# signalgen.net
KiCad netlist of a schematic drawn in EAGLE
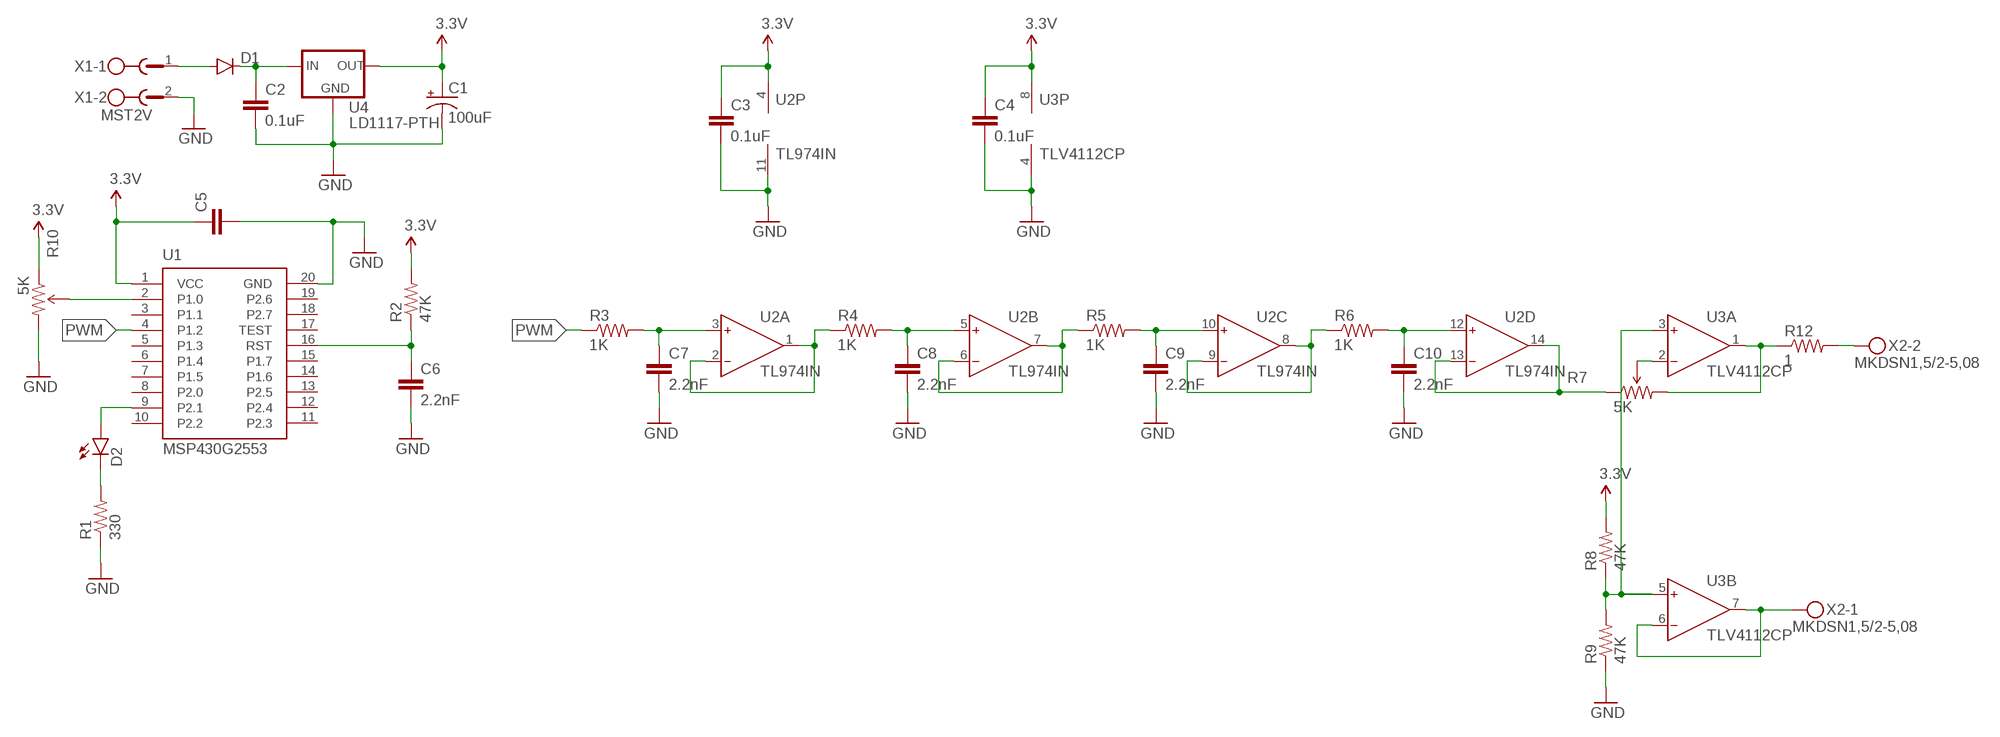
[diagram p0: schematic, sheet 1]

(export (version "E")
  (design (tool "Eeschema 10.0.6"))
  (components
    (comp (ref "C1")
      (value "100uF")
      (footprint "eagle-import:CPOL-RADIAL-100UF-25V")
      (libsource (lib "eagle-import") (part "CAP_POLPTH1"))
    )
    (comp (ref "C2")
      (value "0.1uF")
      (footprint "eagle-import:CAP-PTH-SMALL")
      (libsource (lib "eagle-import") (part "CAPPTH"))
    )
    (comp (ref "C3")
      (value "0.1uF")
      (footprint "eagle-import:CAP-PTH-SMALL")
      (libsource (lib "eagle-import") (part "CAPPTH"))
    )
    (comp (ref "C4")
      (value "0.1uF")
      (footprint "eagle-import:CAP-PTH-SMALL")
      (libsource (lib "eagle-import") (part "CAPPTH"))
    )
    (comp (ref "C5")
      (value "CAPPTH")
      (footprint "eagle-import:CAP-PTH-SMALL")
      (libsource (lib "eagle-import") (part "CAPPTH"))
    )
    (comp (ref "C6")
      (value "2.2nF")
      (footprint "eagle-import:CAP-PTH-SMALL")
      (libsource (lib "eagle-import") (part "CAPPTH"))
    )
    (comp (ref "C7")
      (value "2.2nF")
      (footprint "eagle-import:CAP-PTH-SMALL")
      (libsource (lib "eagle-import") (part "CAPPTH"))
    )
    (comp (ref "C8")
      (value "2.2nF")
      (footprint "eagle-import:CAP-PTH-SMALL")
      (libsource (lib "eagle-import") (part "CAPPTH"))
    )
    (comp (ref "C9")
      (value "2.2nF")
      (footprint "eagle-import:CAP-PTH-SMALL")
      (libsource (lib "eagle-import") (part "CAPPTH"))
    )
    (comp (ref "C10")
      (value "2.2nF")
      (footprint "eagle-import:CAP-PTH-SMALL")
      (libsource (lib "eagle-import") (part "CAPPTH"))
    )
    (comp (ref "D1")
      (value "DIODEPTH")
      (footprint "eagle-import:DIODE-1N4001")
      (libsource (lib "eagle-import") (part "DIODEPTH"))
    )
    (comp (ref "D2")
      (value "LED-3MM-NO_SILK")
      (footprint "eagle-import:LED3MM-NS")
      (libsource (lib "eagle-import") (part "LED-3MM-NO_SILK"))
    )
    (comp (ref "R1")
      (value "330")
      (footprint "eagle-import:AXIAL-0.1")
      (libsource (lib "eagle-import") (part "1KOHM-1/4W-1%(PTH)VERT"))
    )
    (comp (ref "R2")
      (value "47K")
      (footprint "eagle-import:AXIAL-0.3")
      (libsource (lib "eagle-import") (part "1KOHM-1/4W-1%(PTH)"))
    )
    (comp (ref "R3")
      (value "1K")
      (footprint "eagle-import:AXIAL-0.1")
      (libsource (lib "eagle-import") (part "1KOHM-1/4W-1%(PTH)VERT"))
    )
    (comp (ref "R4")
      (value "1K")
      (footprint "eagle-import:AXIAL-0.3")
      (libsource (lib "eagle-import") (part "1KOHM-1/4W-1%(PTH)"))
    )
    (comp (ref "R5")
      (value "1K")
      (footprint "eagle-import:AXIAL-0.1")
      (libsource (lib "eagle-import") (part "1KOHM-1/4W-1%(PTH)VERT"))
    )
    (comp (ref "R6")
      (value "1K")
      (footprint "eagle-import:AXIAL-0.3")
      (libsource (lib "eagle-import") (part "1KOHM-1/4W-1%(PTH)"))
    )
    (comp (ref "R7")
      (value "5K")
      (footprint "eagle-import:TRIM_POT_PTH")
      (libsource (lib "eagle-import") (part "TRIMPOTPTH"))
    )
    (comp (ref "R8")
      (value "47K")
      (footprint "eagle-import:AXIAL-0.3")
      (libsource (lib "eagle-import") (part "1KOHM-1/4W-1%(PTH)"))
    )
    (comp (ref "R9")
      (value "47K")
      (footprint "eagle-import:AXIAL-0.3")
      (libsource (lib "eagle-import") (part "1KOHM-1/4W-1%(PTH)"))
    )
    (comp (ref "R10")
      (value "5K")
      (footprint "eagle-import:TRIM_POT_PTH")
      (libsource (lib "eagle-import") (part "TRIMPOTPTH"))
    )
    (comp (ref "R12")
      (value "1")
      (footprint "eagle-import:AXIAL-0.6")
      (libsource (lib "eagle-import") (part "RESISTORPTH-1W"))
    )
    (comp (ref "U1")
      (value "MSP430G2553")
      (footprint "eagle-import:DIP-20")
      (libsource (lib "eagle-import") (part "MSP430G2553"))
    )
    (comp (ref "U2")
      (value "TL974IN")
      (footprint "eagle-import:DIP-14")
      (libsource (lib "eagle-import") (part "TL974IN"))
    )
    (comp (ref "U3")
      (value "TLV4112CP")
      (footprint "eagle-import:DIP-8")
      (libsource (lib "eagle-import") (part "TLV4112CP"))
    )
    (comp (ref "U4")
      (value "LD1117-PTH")
      (footprint "eagle-import:TO-220ABS")
      (libsource (lib "eagle-import") (part "LD1117-PTH"))
    )
    (comp (ref "X1")
      (value "MST2V")
      (footprint "eagle-import:MSTBV2")
      (libsource (lib "eagle-import") (part "MST2V"))
    )
    (comp (ref "X2")
      (value "MKDSN1,5/2-5,08")
      (footprint "eagle-import:MKDSN1,5_2-5,08")
      (libsource (lib "eagle-import") (part "MKDSN1,5/2-5,08"))
    )
  )
  (nets
    (net (code "1") (name "3.3V") (class "Default")
      (node (ref "C1") (pin "1") (pinfunction "+_1") (pintype "passive"))
      (node (ref "C3") (pin "1") (pinfunction "1_1") (pintype "passive"))
      (node (ref "C4") (pin "1") (pinfunction "1_1") (pintype "passive"))
      (node (ref "C5") (pin "1") (pinfunction "1_1") (pintype "passive"))
      (node (ref "R10") (pin "1") (pinfunction "CCW_1") (pintype "passive"))
      (node (ref "R2") (pin "P$2") (pinfunction "2_P$2") (pintype "passive"))
      (node (ref "R8") (pin "P$2") (pinfunction "2_P$2") (pintype "passive"))
      (node (ref "U1") (pin "1") (pinfunction "VCC_1") (pintype "bidirectional"))
      (node (ref "U2") (pin "4") (pinfunction "V+_4") (pintype "power_in"))
      (node (ref "U3") (pin "8") (pinfunction "V+_8") (pintype "power_in"))
      (node (ref "U4") (pin "2") (pinfunction "OUT_2") (pintype "passive"))
    )
    (net (code "2") (name "GND") (class "Default")
      (node (ref "C1") (pin "2") (pinfunction "-_2") (pintype "passive"))
      (node (ref "C10") (pin "2") (pinfunction "2_2") (pintype "passive"))
      (node (ref "C2") (pin "2") (pinfunction "2_2") (pintype "passive"))
      (node (ref "C3") (pin "2") (pinfunction "2_2") (pintype "passive"))
      (node (ref "C4") (pin "2") (pinfunction "2_2") (pintype "passive"))
      (node (ref "C5") (pin "2") (pinfunction "2_2") (pintype "passive"))
      (node (ref "C6") (pin "2") (pinfunction "2_2") (pintype "passive"))
      (node (ref "C7") (pin "2") (pinfunction "2_2") (pintype "passive"))
      (node (ref "C8") (pin "2") (pinfunction "2_2") (pintype "passive"))
      (node (ref "C9") (pin "2") (pinfunction "2_2") (pintype "passive"))
      (node (ref "R1") (pin "P$1") (pinfunction "1_P$1") (pintype "passive"))
      (node (ref "R10") (pin "3") (pinfunction "CW_3") (pintype "passive"))
      (node (ref "R9") (pin "P$1") (pinfunction "1_P$1") (pintype "passive"))
      (node (ref "U1") (pin "20") (pinfunction "GND_20") (pintype "bidirectional"))
      (node (ref "U2") (pin "11") (pinfunction "V-_11") (pintype "power_in"))
      (node (ref "U3") (pin "4") (pinfunction "V-_4") (pintype "power_in"))
      (node (ref "U4") (pin "1") (pinfunction "GND_1") (pintype "input"))
      (node (ref "X1") (pin "2") (pinfunction "1_2") (pintype "passive"))
    )
    (net (code "3") (name "Net-(D1-PadA)") (class "Default")
      (node (ref "D1") (pin "A") (pinfunction "A_A") (pintype "passive"))
      (node (ref "X1") (pin "1") (pinfunction "1_1") (pintype "passive"))
    )
    (net (code "4") (name "Net-(D2-C)") (class "Default")
      (node (ref "D2") (pin "K") (pinfunction "C_K") (pintype "passive"))
      (node (ref "R1") (pin "P$2") (pinfunction "2_P$2") (pintype "passive"))
    )
    (net (code "5") (name "Net-(R2-1)") (class "Default")
      (node (ref "C6") (pin "1") (pinfunction "1_1") (pintype "passive"))
      (node (ref "R2") (pin "P$1") (pinfunction "1_P$1") (pintype "passive"))
      (node (ref "U1") (pin "16") (pinfunction "RST_16") (pintype "bidirectional"))
    )
    (net (code "6") (name "Net-(R3-2)") (class "Default")
      (node (ref "C7") (pin "1") (pinfunction "1_1") (pintype "passive"))
      (node (ref "R3") (pin "P$2") (pinfunction "2_P$2") (pintype "passive"))
      (node (ref "U2") (pin "3") (pinfunction "IN+_3") (pintype "input"))
    )
    (net (code "7") (name "Net-(R4-1)") (class "Default")
      (node (ref "R4") (pin "P$1") (pinfunction "1_P$1") (pintype "passive"))
      (node (ref "U2") (pin "1") (pinfunction "OUT_1") (pintype "output"))
      (node (ref "U2") (pin "2") (pinfunction "IN-_2") (pintype "input"))
    )
    (net (code "8") (name "Net-(R4-2)") (class "Default")
      (node (ref "C8") (pin "1") (pinfunction "1_1") (pintype "passive"))
      (node (ref "R4") (pin "P$2") (pinfunction "2_P$2") (pintype "passive"))
      (node (ref "U2") (pin "5") (pinfunction "IN+_5") (pintype "input"))
    )
    (net (code "9") (name "Net-(R5-1)") (class "Default")
      (node (ref "R5") (pin "P$1") (pinfunction "1_P$1") (pintype "passive"))
      (node (ref "U2") (pin "6") (pinfunction "IN-_6") (pintype "input"))
      (node (ref "U2") (pin "7") (pinfunction "OUT_7") (pintype "output"))
    )
    (net (code "10") (name "Net-(R5-2)") (class "Default")
      (node (ref "C9") (pin "1") (pinfunction "1_1") (pintype "passive"))
      (node (ref "R5") (pin "P$2") (pinfunction "2_P$2") (pintype "passive"))
      (node (ref "U2") (pin "10") (pinfunction "IN+_10") (pintype "input"))
    )
    (net (code "11") (name "Net-(R6-1)") (class "Default")
      (node (ref "R6") (pin "P$1") (pinfunction "1_P$1") (pintype "passive"))
      (node (ref "U2") (pin "8") (pinfunction "OUT_8") (pintype "output"))
      (node (ref "U2") (pin "9") (pinfunction "IN-_9") (pintype "input"))
    )
    (net (code "12") (name "Net-(R6-2)") (class "Default")
      (node (ref "C10") (pin "1") (pinfunction "1_1") (pintype "passive"))
      (node (ref "R6") (pin "P$2") (pinfunction "2_P$2") (pintype "passive"))
      (node (ref "U2") (pin "12") (pinfunction "IN+_12") (pintype "input"))
    )
    (net (code "13") (name "Net-(R7-CCW)") (class "Default")
      (node (ref "R7") (pin "1") (pinfunction "CCW_1") (pintype "passive"))
      (node (ref "U2") (pin "13") (pinfunction "IN-_13") (pintype "input"))
      (node (ref "U2") (pin "14") (pinfunction "OUT_14") (pintype "output"))
    )
    (net (code "14") (name "Net-(R7-WIPER)") (class "Default")
      (node (ref "R7") (pin "2") (pinfunction "WIPER_2") (pintype "passive"))
      (node (ref "U3") (pin "2") (pinfunction "IN-_2") (pintype "input"))
    )
    (net (code "15") (name "Net-(R8-1)") (class "Default")
      (node (ref "R8") (pin "P$1") (pinfunction "1_P$1") (pintype "passive"))
      (node (ref "R9") (pin "P$2") (pinfunction "2_P$2") (pintype "passive"))
      (node (ref "U3") (pin "3") (pinfunction "IN+_3") (pintype "input"))
      (node (ref "U3") (pin "5") (pinfunction "IN+_5") (pintype "input"))
    )
    (net (code "16") (name "Net-(R10-WIPER)") (class "Default")
      (node (ref "R10") (pin "2") (pinfunction "WIPER_2") (pintype "passive"))
      (node (ref "U1") (pin "2") (pinfunction "P1.0_2") (pintype "bidirectional"))
    )
    (net (code "17") (name "Net-(R12-1)") (class "Default")
      (node (ref "R12") (pin "P$1") (pinfunction "1_P$1") (pintype "passive"))
      (node (ref "R7") (pin "3") (pinfunction "CW_3") (pintype "passive"))
      (node (ref "U3") (pin "1") (pinfunction "OUT_1") (pintype "output"))
    )
    (net (code "18") (name "Net-(R12-2)") (class "Default")
      (node (ref "R12") (pin "P$2") (pinfunction "2_P$2") (pintype "passive"))
      (node (ref "X2") (pin "2") (pinfunction "KL_2") (pintype "passive"))
    )
    (net (code "19") (name "Net-(U1-P2.1)") (class "Default")
      (node (ref "D2") (pin "A") (pinfunction "A_A") (pintype "passive"))
      (node (ref "U1") (pin "9") (pinfunction "P2.1_9") (pintype "bidirectional"))
    )
    (net (code "20") (name "Net-(U3B-IN-)") (class "Default")
      (node (ref "U3") (pin "6") (pinfunction "IN-_6") (pintype "input"))
      (node (ref "U3") (pin "7") (pinfunction "OUT_7") (pintype "output"))
      (node (ref "X2") (pin "1") (pinfunction "KL_1") (pintype "passive"))
    )
    (net (code "21") (name "Net-(U4-IN)") (class "Default")
      (node (ref "C2") (pin "1") (pinfunction "1_1") (pintype "passive"))
      (node (ref "D1") (pin "C") (pinfunction "C_C") (pintype "passive"))
      (node (ref "U4") (pin "3") (pinfunction "IN_3") (pintype "input"))
    )
    (net (code "22") (name "PWM") (class "Default")
      (node (ref "R3") (pin "P$1") (pinfunction "1_P$1") (pintype "passive"))
      (node (ref "U1") (pin "4") (pinfunction "P1.2_4") (pintype "bidirectional"))
    )
    (net (code "23") (name "unconnected-(U1-P1.1-Pad3)") (class "Default")
      (node (ref "U1") (pin "3") (pinfunction "P1.1_3") (pintype "bidirectional"))
    )
    (net (code "24") (name "unconnected-(U1-P1.3-Pad5)") (class "Default")
      (node (ref "U1") (pin "5") (pinfunction "P1.3_5") (pintype "bidirectional"))
    )
    (net (code "25") (name "unconnected-(U1-P1.4-Pad6)") (class "Default")
      (node (ref "U1") (pin "6") (pinfunction "P1.4_6") (pintype "bidirectional"))
    )
    (net (code "26") (name "unconnected-(U1-P1.5-Pad7)") (class "Default")
      (node (ref "U1") (pin "7") (pinfunction "P1.5_7") (pintype "bidirectional"))
    )
    (net (code "27") (name "unconnected-(U1-P1.6-Pad14)") (class "Default")
      (node (ref "U1") (pin "14") (pinfunction "P1.6_14") (pintype "bidirectional"))
    )
    (net (code "28") (name "unconnected-(U1-P1.7-Pad15)") (class "Default")
      (node (ref "U1") (pin "15") (pinfunction "P1.7_15") (pintype "bidirectional"))
    )
    (net (code "29") (name "unconnected-(U1-P2.0-Pad8)") (class "Default")
      (node (ref "U1") (pin "8") (pinfunction "P2.0_8") (pintype "bidirectional"))
    )
    (net (code "30") (name "unconnected-(U1-P2.2-Pad10)") (class "Default")
      (node (ref "U1") (pin "10") (pinfunction "P2.2_10") (pintype "bidirectional"))
    )
    (net (code "31") (name "unconnected-(U1-P2.3-Pad11)") (class "Default")
      (node (ref "U1") (pin "11") (pinfunction "P2.3_11") (pintype "bidirectional"))
    )
    (net (code "32") (name "unconnected-(U1-P2.4-Pad12)") (class "Default")
      (node (ref "U1") (pin "12") (pinfunction "P2.4_12") (pintype "bidirectional"))
    )
    (net (code "33") (name "unconnected-(U1-P2.5-Pad13)") (class "Default")
      (node (ref "U1") (pin "13") (pinfunction "P2.5_13") (pintype "bidirectional"))
    )
    (net (code "34") (name "unconnected-(U1-P2.6-Pad19)") (class "Default")
      (node (ref "U1") (pin "19") (pinfunction "P2.6_19") (pintype "bidirectional"))
    )
    (net (code "35") (name "unconnected-(U1-P2.7-Pad18)") (class "Default")
      (node (ref "U1") (pin "18") (pinfunction "P2.7_18") (pintype "bidirectional"))
    )
    (net (code "36") (name "unconnected-(U1-TEST-Pad17)") (class "Default")
      (node (ref "U1") (pin "17") (pinfunction "TEST_17") (pintype "bidirectional"))
    )
  )
)
